# foot-switch_board_01.net
KiCad netlist of a schematic drawn in Altium Designer
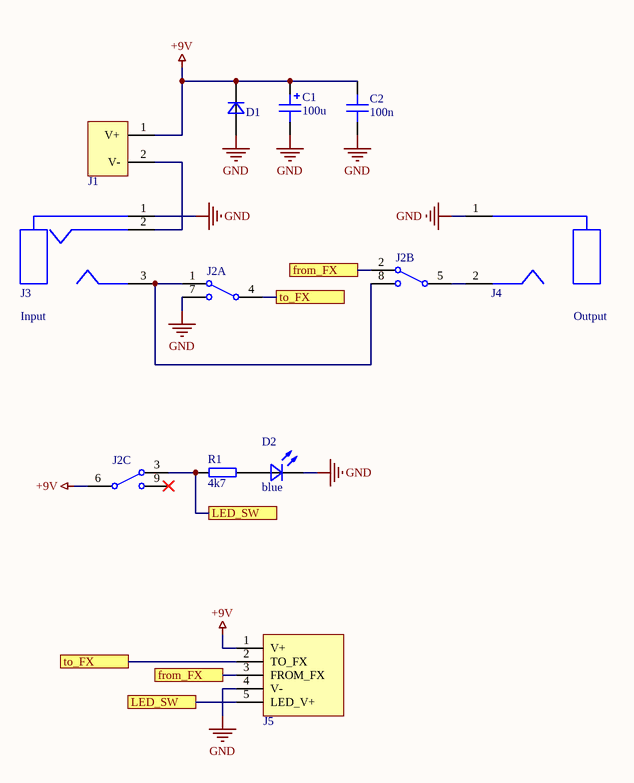
[diagram p0: foot-switch_board_01.SchDoc]

(export (version "E")
  (design (tool "Eeschema 10.0.6"))
  (components
    (comp (ref "C1")
      (value "100u")
      (footprint "pol_cap_2x5x11_0.5_rad_flat")
      (fields (field (name "Comment") "pol_cap_tht_2x5x11_flat"))
      (libsource (lib "mycomponents") (part "pol_cap_tht_2x5x11_flat"))
    )
    (comp (ref "C2")
      (value "100n")
      (footprint "CAP_5mm")
      (description "ceramic cap\r\nAnschlussabstand: 5mm\r\n0.5mm lead diameter")
      (fields (field (name "Comment") "cap_tht_5mm"))
      (libsource (lib "mycomponents") (part "cap_tht_5mm"))
    )
    (comp (ref "D1")
      (value "diode_tht_1n4007")
      (footprint "diode_tht")
      (fields (field (name "MANUFACTURER") "onsemi") (field (name "MANUFACTURER PART NUMBER") "1N4007RLG"))
      (libsource (lib "mycomponents") (part "diode_tht_1n4007"))
    )
    (comp (ref "D2")
      (value "blue")
      (footprint "led_3mm")
      (description "Durchlassstrom If: 20mA\r\nDurchlassspannung: 3.7V")
      (fields
        (field (name "MANUFACTURER") "Forge")
        (field (name "MANUFACTURER PART NUMBER") "FNL-U300B22CDSL")
      )
      (libsource (lib "mycomponents") (part "led_blue_tht_3mm"))
    )
    (comp (ref "J1")
      (value "2 Pole 2.54mm")
      (footprint "2.54mm_2pole")
      (description "Solder contacts for a 2.54mm connector")
      (libsource (lib "mycomponents") (part "2 Pole 2.54mm"))
    )
    (comp (ref "J2")
      (value "SF17010F-0302-21R-L")
      (footprint "SF17010F-0302-21R-L")
      (description "Alpha Footswitch 3PDT, PCB")
      (fields (field (name "MANUFACTURER") "Alpha"))
      (libsource (lib "mycomponents") (part "Alpha 3PDT Footswitch PCB"))
    )
    (comp (ref "J3")
      (value "Audio Jack 6mm 3 pole contacts")
      (footprint "2.54mm_3pole")
      (description "Solder contacts for a 6mm stereo audio jack")
      (libsource (lib "mycomponents") (part "Audio Jack 6mm 3 pole contacts"))
    )
    (comp (ref "J4")
      (value "Audio Jack 6mm 2 pole contacts")
      (footprint "2.54mm_2pole")
      (description "Solder contacts for a 6mm mono audio jack")
      (libsource (lib "mycomponents") (part "Audio Jack 6mm 2 pole contacts"))
    )
    (comp (ref "J5")
      (value "5 Pole Ribbon Connector")
      (footprint "1.27mm_5pole_edge")
      (description "Solder contacts for a 1.27mm ribbon cable")
      (libsource (lib "mycomponents") (part "5 Pole Ribbon Connector"))
    )
    (comp (ref "R1")
      (value "4k7")
      (footprint "res_P10mm_axial")
      (description "metal oxide\r\nProduktpalette: MCMF\r\nProduktdurchmesser: 2.5mm\r\nProduktlänge: 6.8mm")
      (fields
        (field (name "MANUFACTURER") "Multicomp Pro")
        (field (name "MANUFACTURER PART NUMBER") "MCMF006FF1002A50")
      )
      (libsource (lib "mycomponents") (part "res_mcmf_series_tht_axial_P10mm"))
    )
  )
  (nets
    (net (code "1") (name "+9V") (class "Default")
      (node (ref "C1") (pin "1") (pinfunction "1_1") (pintype "passive"))
      (node (ref "C2") (pin "2") (pinfunction "2_2") (pintype "passive"))
      (node (ref "D1") (pin "2") (pinfunction "2_2") (pintype "passive"))
      (node (ref "J1") (pin "1") (pinfunction "V+_1") (pintype "passive"))
      (node (ref "J2") (pin "6") (pinfunction "6_6") (pintype "passive"))
      (node (ref "J5") (pin "1") (pinfunction "V+_1") (pintype "passive"))
    )
    (net (code "2") (name "/LED_SW") (class "Default")
      (node (ref "J2") (pin "3") (pinfunction "3_3") (pintype "passive"))
      (node (ref "J5") (pin "5") (pinfunction "LED_V+_5") (pintype "passive"))
      (node (ref "R1") (pin "1") (pinfunction "1_1") (pintype "passive"))
    )
    (net (code "3") (name "/from_FX") (class "Default")
      (node (ref "J2") (pin "2") (pinfunction "2_2") (pintype "passive"))
      (node (ref "J5") (pin "3") (pinfunction "FROM_FX_3") (pintype "passive"))
    )
    (net (code "4") (name "/to_FX") (class "Default")
      (node (ref "J2") (pin "4") (pinfunction "4_4") (pintype "passive"))
      (node (ref "J5") (pin "2") (pinfunction "TO_FX_2") (pintype "passive"))
    )
    (net (code "5") (name "GND") (class "Default")
      (node (ref "C1") (pin "2") (pinfunction "2_2") (pintype "passive"))
      (node (ref "C2") (pin "1") (pinfunction "1_1") (pintype "passive"))
      (node (ref "D1") (pin "1") (pinfunction "1_1") (pintype "passive"))
      (node (ref "D2") (pin "2") (pinfunction "kathode_2") (pintype "passive"))
      (node (ref "J2") (pin "7") (pinfunction "7_7") (pintype "passive"))
      (node (ref "J3") (pin "1") (pinfunction "1_1") (pintype "passive"))
      (node (ref "J4") (pin "1") (pinfunction "1_1") (pintype "passive"))
      (node (ref "J5") (pin "4") (pinfunction "V-_4") (pintype "passive"))
    )
    (net (code "6") (name "Net-(D2-anode)") (class "Default")
      (node (ref "D2") (pin "1") (pinfunction "anode_1") (pintype "passive"))
      (node (ref "R1") (pin "2") (pinfunction "2_2") (pintype "passive"))
    )
    (net (code "7") (name "Net-(J1-V-)") (class "Default")
      (node (ref "J1") (pin "2") (pinfunction "V-_2") (pintype "passive"))
      (node (ref "J3") (pin "2") (pinfunction "2_2") (pintype "passive"))
    )
    (net (code "8") (name "Net-(J2-Pad1)") (class "Default")
      (node (ref "J2") (pin "1") (pinfunction "1_1") (pintype "passive"))
      (node (ref "J2") (pin "8") (pinfunction "8_8") (pintype "passive"))
      (node (ref "J3") (pin "3") (pinfunction "3_3") (pintype "passive"))
    )
    (net (code "9") (name "Net-(J2-Pad5)") (class "Default")
      (node (ref "J2") (pin "5") (pinfunction "5_5") (pintype "passive"))
      (node (ref "J4") (pin "2") (pinfunction "2_2") (pintype "passive"))
    )
    (net (code "10") (name "unconnected-(J2-Pad9)") (class "Default")
      (node (ref "J2") (pin "9") (pinfunction "9_9") (pintype "passive+no_connect"))
    )
  )
)
